# Amplifier_6Channels__2024-06-29.net
KiCad netlist of a schematic drawn in EasyEDA Pro
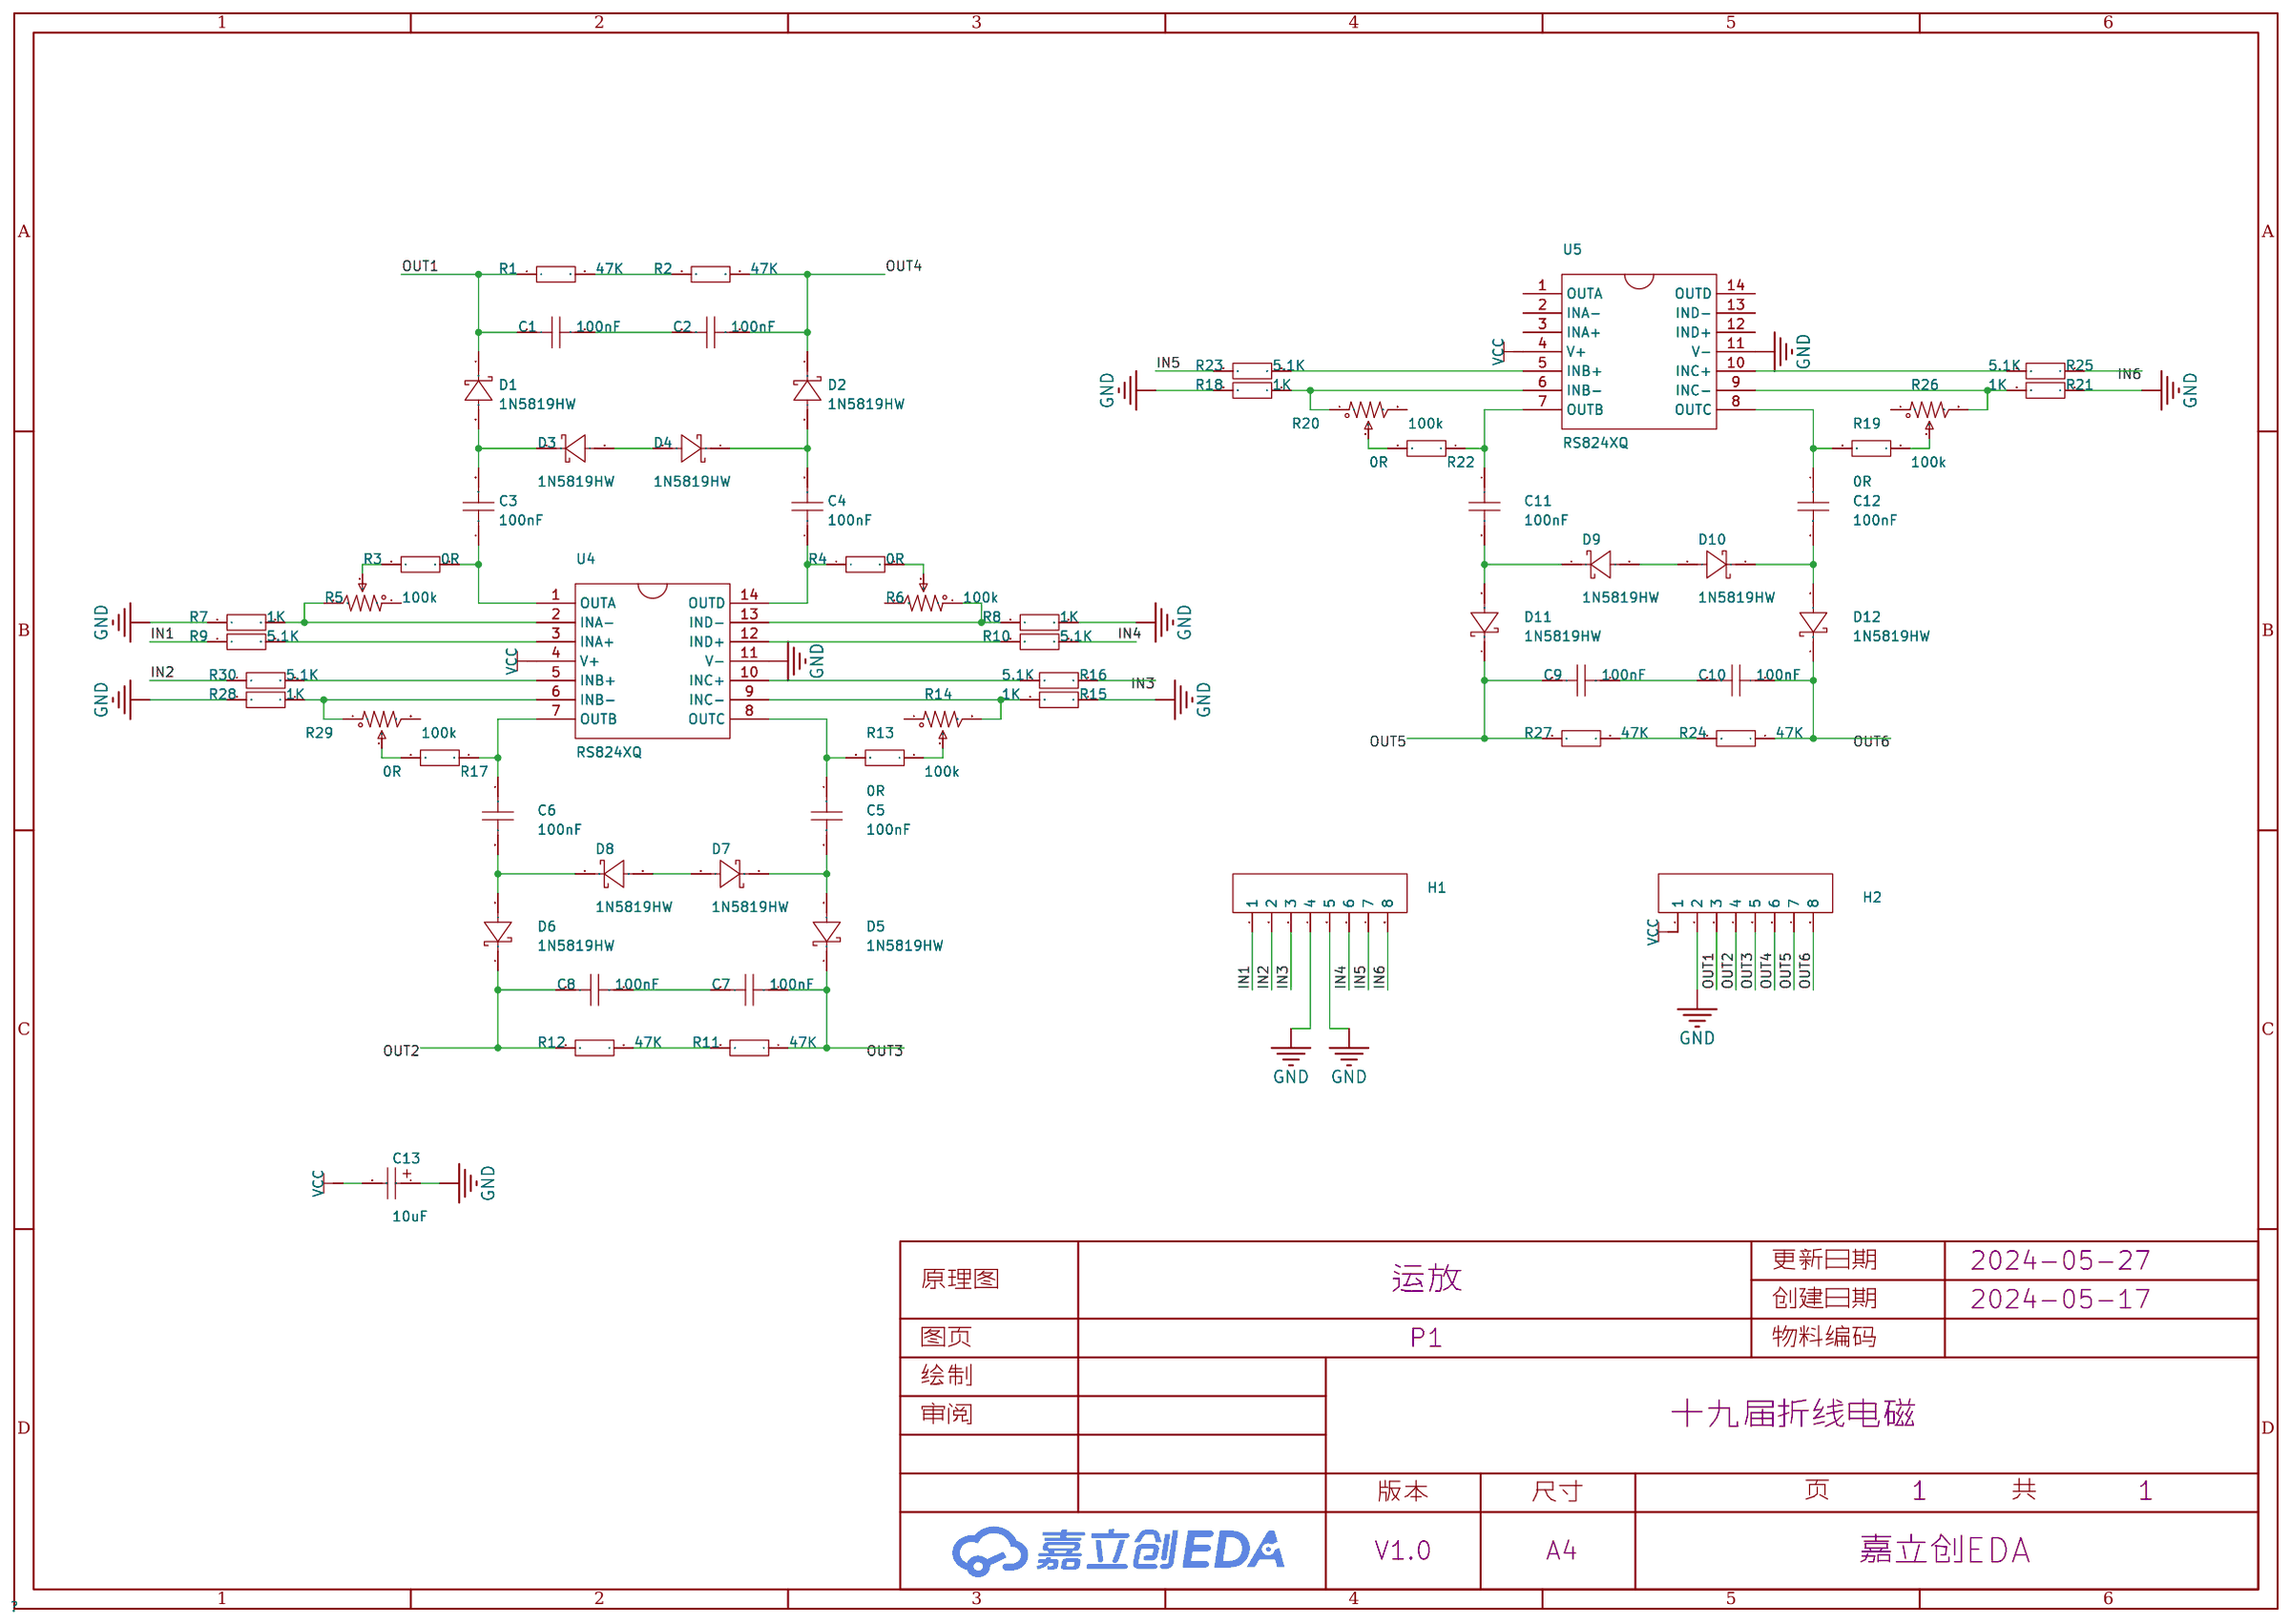
[diagram p0: schematic sheet]

(export (version "E")
  (design (tool "Eeschema 10.0.6"))
  (components
    (comp (ref "C1")
      (value "100nF")
      (footprint "easyedapro:C0603")
      (libsource (lib "easyedapro") (part "CapAcitance"))
    )
    (comp (ref "C2")
      (value "100nF")
      (footprint "easyedapro:C0603")
      (libsource (lib "easyedapro") (part "CapAcitance"))
    )
    (comp (ref "C3")
      (value "100nF")
      (footprint "easyedapro:C0603")
      (libsource (lib "easyedapro") (part "CapAcitance"))
    )
    (comp (ref "C4")
      (value "100nF")
      (footprint "easyedapro:C0603")
      (libsource (lib "easyedapro") (part "CapAcitance"))
    )
    (comp (ref "C5")
      (value "100nF")
      (footprint "easyedapro:C0603")
      (libsource (lib "easyedapro") (part "CapAcitance"))
    )
    (comp (ref "C6")
      (value "100nF")
      (footprint "easyedapro:C0603")
      (libsource (lib "easyedapro") (part "CapAcitance"))
    )
    (comp (ref "C7")
      (value "100nF")
      (footprint "easyedapro:C0603")
      (libsource (lib "easyedapro") (part "CapAcitance"))
    )
    (comp (ref "C8")
      (value "100nF")
      (footprint "easyedapro:C0603")
      (libsource (lib "easyedapro") (part "CapAcitance"))
    )
    (comp (ref "C9")
      (value "100nF")
      (footprint "easyedapro:C0603")
      (libsource (lib "easyedapro") (part "CapAcitance"))
    )
    (comp (ref "C10")
      (value "100nF")
      (footprint "easyedapro:C0603")
      (libsource (lib "easyedapro") (part "CapAcitance"))
    )
    (comp (ref "C11")
      (value "100nF")
      (footprint "easyedapro:C0603")
      (libsource (lib "easyedapro") (part "CapAcitance"))
    )
    (comp (ref "C12")
      (value "100nF")
      (footprint "easyedapro:C0603")
      (libsource (lib "easyedapro") (part "CapAcitance"))
    )
    (comp (ref "C13")
      (value "10uF")
      (footprint "easyedapro:CAP-SMD_L3.2-W1.6-RD-C7171")
      (description "容值:10uF;精度:±10%;额定电压:16V;等效串联电阻:3Ω@100kHz;")
      (fields (field (name "Manufacturer Part") "TAJA106K016RNJ") (field (name "Manufacturer") "Kyocera AVX"))
      (libsource (lib "easyedapro") (part "TAJA106K016RNJ"))
    )
    (comp (ref "D1")
      (value "1N5819HW")
      (footprint "easyedapro:SOD-123_L2.7-W1.6-LS3.7-RD-1")
      (description "二极管配置:-;正向压降(Vf):900mV@3A;直流反向耐压(Vr):40V;平均整流电流(Io):1A;")
      (fields (field (name "Manufacturer") "TECH PUBLIC(台舟)"))
      (libsource (lib "easyedapro") (part "1N5819HW"))
    )
    (comp (ref "D2")
      (value "1N5819HW")
      (footprint "easyedapro:SOD-123_L2.7-W1.6-LS3.7-RD-1")
      (description "二极管配置:-;正向压降(Vf):900mV@3A;直流反向耐压(Vr):40V;平均整流电流(Io):1A;")
      (fields (field (name "Manufacturer") "TECH PUBLIC(台舟)"))
      (libsource (lib "easyedapro") (part "1N5819HW"))
    )
    (comp (ref "D3")
      (value "1N5819HW")
      (footprint "easyedapro:SOD-123_L2.7-W1.6-LS3.7-RD-1")
      (description "二极管配置:-;正向压降(Vf):900mV@3A;直流反向耐压(Vr):40V;平均整流电流(Io):1A;")
      (fields (field (name "Manufacturer") "TECH PUBLIC(台舟)"))
      (libsource (lib "easyedapro") (part "1N5819HW"))
    )
    (comp (ref "D4")
      (value "1N5819HW")
      (footprint "easyedapro:SOD-123_L2.7-W1.6-LS3.7-RD-1")
      (description "二极管配置:-;正向压降(Vf):900mV@3A;直流反向耐压(Vr):40V;平均整流电流(Io):1A;")
      (fields (field (name "Manufacturer") "TECH PUBLIC(台舟)"))
      (libsource (lib "easyedapro") (part "1N5819HW"))
    )
    (comp (ref "D5")
      (value "1N5819HW")
      (footprint "easyedapro:SOD-123_L2.7-W1.6-LS3.7-RD-1")
      (description "二极管配置:-;正向压降(Vf):900mV@3A;直流反向耐压(Vr):40V;平均整流电流(Io):1A;")
      (fields (field (name "Manufacturer") "TECH PUBLIC(台舟)"))
      (libsource (lib "easyedapro") (part "1N5819HW"))
    )
    (comp (ref "D6")
      (value "1N5819HW")
      (footprint "easyedapro:SOD-123_L2.7-W1.6-LS3.7-RD-1")
      (description "二极管配置:-;正向压降(Vf):900mV@3A;直流反向耐压(Vr):40V;平均整流电流(Io):1A;")
      (fields (field (name "Manufacturer") "TECH PUBLIC(台舟)"))
      (libsource (lib "easyedapro") (part "1N5819HW"))
    )
    (comp (ref "D7")
      (value "1N5819HW")
      (footprint "easyedapro:SOD-123_L2.7-W1.6-LS3.7-RD-1")
      (description "二极管配置:-;正向压降(Vf):900mV@3A;直流反向耐压(Vr):40V;平均整流电流(Io):1A;")
      (fields (field (name "Manufacturer") "TECH PUBLIC(台舟)"))
      (libsource (lib "easyedapro") (part "1N5819HW"))
    )
    (comp (ref "D8")
      (value "1N5819HW")
      (footprint "easyedapro:SOD-123_L2.7-W1.6-LS3.7-RD-1")
      (description "二极管配置:-;正向压降(Vf):900mV@3A;直流反向耐压(Vr):40V;平均整流电流(Io):1A;")
      (fields (field (name "Manufacturer") "TECH PUBLIC(台舟)"))
      (libsource (lib "easyedapro") (part "1N5819HW"))
    )
    (comp (ref "D9")
      (value "1N5819HW")
      (footprint "easyedapro:SOD-123_L2.7-W1.6-LS3.7-RD-1")
      (description "二极管配置:-;正向压降(Vf):900mV@3A;直流反向耐压(Vr):40V;平均整流电流(Io):1A;")
      (fields (field (name "Manufacturer") "TECH PUBLIC(台舟)"))
      (libsource (lib "easyedapro") (part "1N5819HW"))
    )
    (comp (ref "D10")
      (value "1N5819HW")
      (footprint "easyedapro:SOD-123_L2.7-W1.6-LS3.7-RD-1")
      (description "二极管配置:-;正向压降(Vf):900mV@3A;直流反向耐压(Vr):40V;平均整流电流(Io):1A;")
      (fields (field (name "Manufacturer") "TECH PUBLIC(台舟)"))
      (libsource (lib "easyedapro") (part "1N5819HW"))
    )
    (comp (ref "D11")
      (value "1N5819HW")
      (footprint "easyedapro:SOD-123_L2.7-W1.6-LS3.7-RD-1")
      (description "二极管配置:-;正向压降(Vf):900mV@3A;直流反向耐压(Vr):40V;平均整流电流(Io):1A;")
      (fields (field (name "Manufacturer") "TECH PUBLIC(台舟)"))
      (libsource (lib "easyedapro") (part "1N5819HW"))
    )
    (comp (ref "D12")
      (value "1N5819HW")
      (footprint "easyedapro:SOD-123_L2.7-W1.6-LS3.7-RD-1")
      (description "二极管配置:-;正向压降(Vf):900mV@3A;直流反向耐压(Vr):40V;平均整流电流(Io):1A;")
      (fields (field (name "Manufacturer") "TECH PUBLIC(台舟)"))
      (libsource (lib "easyedapro") (part "1N5819HW"))
    )
    (comp (ref "H1")
      (value "~")
      (footprint "easyedapro:HDR-TH_8P-P2.54-V-F-1")
      (libsource (lib "easyedapro") (part "Header-Female-2.54_1x8"))
    )
    (comp (ref "H2")
      (value "~")
      (footprint "easyedapro:HDR-TH_8P-P2.54-V-F-1")
      (libsource (lib "easyedapro") (part "Header-Female-2.54_1x8"))
    )
    (comp (ref "R1") (value "47K") (footprint "easyedapro:R0603") (libsource (lib "easyedapro") (part "电阻")))
    (comp (ref "R2") (value "47K") (footprint "easyedapro:R0603") (libsource (lib "easyedapro") (part "电阻")))
    (comp (ref "R3") (value "0R") (footprint "easyedapro:R0603") (libsource (lib "easyedapro") (part "电阻")))
    (comp (ref "R4") (value "0R") (footprint "easyedapro:R0603") (libsource (lib "easyedapro") (part "电阻")))
    (comp (ref "R5")
      (value "100k")
      (footprint "easyedapro:RES-ADJ-TH_3P-L9.5-W4.85-P2.50-BL-BS")
      (description "阻值:50kΩ;精度:±10%;")
      (fields (field (name "Manufacturer Part") "3296W-1-503") (field (name "Manufacturer") "BOCHEN(博晨)"))
      (libsource (lib "easyedapro") (part "可调电阻"))
    )
    (comp (ref "R6")
      (value "100k")
      (footprint "easyedapro:RES-ADJ-TH_3P-L9.5-W4.85-P2.50-BL-BS")
      (description "阻值:50kΩ;精度:±10%;")
      (fields (field (name "Manufacturer Part") "3296W-1-503") (field (name "Manufacturer") "BOCHEN(博晨)"))
      (libsource (lib "easyedapro") (part "可调电阻"))
    )
    (comp (ref "R7") (value "1K") (footprint "easyedapro:R0603") (libsource (lib "easyedapro") (part "电阻")))
    (comp (ref "R8") (value "1K") (footprint "easyedapro:R0603") (libsource (lib "easyedapro") (part "电阻")))
    (comp (ref "R9") (value "5.1K") (footprint "easyedapro:R0603") (libsource (lib "easyedapro") (part "电阻")))
    (comp (ref "R10")
      (value "5.1K")
      (footprint "easyedapro:R0603")
      (libsource (lib "easyedapro") (part "电阻"))
    )
    (comp (ref "R11") (value "47K") (footprint "easyedapro:R0603") (libsource (lib "easyedapro") (part "电阻")))
    (comp (ref "R12") (value "47K") (footprint "easyedapro:R0603") (libsource (lib "easyedapro") (part "电阻")))
    (comp (ref "R13") (value "0R") (footprint "easyedapro:R0603") (libsource (lib "easyedapro") (part "电阻")))
    (comp (ref "R14")
      (value "100k")
      (footprint "easyedapro:RES-ADJ-TH_3P-L9.5-W4.85-P2.50-BL-BS")
      (description "阻值:50kΩ;精度:±10%;")
      (fields (field (name "Manufacturer Part") "3296W-1-503") (field (name "Manufacturer") "BOCHEN(博晨)"))
      (libsource (lib "easyedapro") (part "可调电阻"))
    )
    (comp (ref "R15") (value "1K") (footprint "easyedapro:R0603") (libsource (lib "easyedapro") (part "电阻")))
    (comp (ref "R16")
      (value "5.1K")
      (footprint "easyedapro:R0603")
      (libsource (lib "easyedapro") (part "电阻"))
    )
    (comp (ref "R17") (value "0R") (footprint "easyedapro:R0603") (libsource (lib "easyedapro") (part "电阻")))
    (comp (ref "R18") (value "1K") (footprint "easyedapro:R0603") (libsource (lib "easyedapro") (part "电阻")))
    (comp (ref "R19") (value "0R") (footprint "easyedapro:R0603") (libsource (lib "easyedapro") (part "电阻")))
    (comp (ref "R20")
      (value "100k")
      (footprint "easyedapro:RES-ADJ-TH_3P-L9.5-W4.85-P2.50-BL-BS")
      (description "阻值:50kΩ;精度:±10%;")
      (fields (field (name "Manufacturer Part") "3296W-1-503") (field (name "Manufacturer") "BOCHEN(博晨)"))
      (libsource (lib "easyedapro") (part "可调电阻"))
    )
    (comp (ref "R21") (value "1K") (footprint "easyedapro:R0603") (libsource (lib "easyedapro") (part "电阻")))
    (comp (ref "R22") (value "0R") (footprint "easyedapro:R0603") (libsource (lib "easyedapro") (part "电阻")))
    (comp (ref "R23")
      (value "5.1K")
      (footprint "easyedapro:R0603")
      (libsource (lib "easyedapro") (part "电阻"))
    )
    (comp (ref "R24") (value "47K") (footprint "easyedapro:R0603") (libsource (lib "easyedapro") (part "电阻")))
    (comp (ref "R25")
      (value "5.1K")
      (footprint "easyedapro:R0603")
      (libsource (lib "easyedapro") (part "电阻"))
    )
    (comp (ref "R26")
      (value "100k")
      (footprint "easyedapro:RES-ADJ-TH_3P-L9.5-W4.85-P2.50-BL-BS")
      (description "阻值:50kΩ;精度:±10%;")
      (fields (field (name "Manufacturer Part") "3296W-1-503") (field (name "Manufacturer") "BOCHEN(博晨)"))
      (libsource (lib "easyedapro") (part "可调电阻"))
    )
    (comp (ref "R27") (value "47K") (footprint "easyedapro:R0603") (libsource (lib "easyedapro") (part "电阻")))
    (comp (ref "R28") (value "1K") (footprint "easyedapro:R0603") (libsource (lib "easyedapro") (part "电阻")))
    (comp (ref "R29")
      (value "100k")
      (footprint "easyedapro:RES-ADJ-TH_3P-L9.5-W4.85-P2.50-BL-BS")
      (description "阻值:50kΩ;精度:±10%;")
      (fields (field (name "Manufacturer Part") "3296W-1-503") (field (name "Manufacturer") "BOCHEN(博晨)"))
      (libsource (lib "easyedapro") (part "可调电阻"))
    )
    (comp (ref "R30")
      (value "5.1K")
      (footprint "easyedapro:R0603")
      (libsource (lib "easyedapro") (part "电阻"))
    )
    (comp (ref "U4")
      (value "RS824XQ")
      (footprint "easyedapro:TSSOP-14")
      (libsource (lib "easyedapro") (part "RS824XQ"))
    )
    (comp (ref "U5")
      (value "RS824XQ")
      (footprint "easyedapro:TSSOP-14")
      (libsource (lib "easyedapro") (part "RS824XQ"))
    )
  )
  (nets
    (net (code "1") (name "/IN1") (class "Default")
      (node (ref "H1") (pin "1") (pinfunction "1_1") (pintype "input"))
      (node (ref "R9") (pin "1") (pinfunction "1_1") (pintype "input"))
    )
    (net (code "2") (name "/IN2") (class "Default")
      (node (ref "H1") (pin "2") (pinfunction "2_2") (pintype "input"))
      (node (ref "R30") (pin "1") (pinfunction "1_1") (pintype "input"))
    )
    (net (code "3") (name "/IN3") (class "Default")
      (node (ref "H1") (pin "3") (pinfunction "3_3") (pintype "input"))
      (node (ref "R16") (pin "1") (pinfunction "1_1") (pintype "input"))
    )
    (net (code "4") (name "/IN4") (class "Default")
      (node (ref "H1") (pin "6") (pinfunction "6_6") (pintype "input"))
      (node (ref "R10") (pin "1") (pinfunction "1_1") (pintype "input"))
    )
    (net (code "5") (name "/IN5") (class "Default")
      (node (ref "H1") (pin "7") (pinfunction "7_7") (pintype "input"))
      (node (ref "R23") (pin "1") (pinfunction "1_1") (pintype "input"))
    )
    (net (code "6") (name "/IN6") (class "Default")
      (node (ref "H1") (pin "8") (pinfunction "8_8") (pintype "input"))
      (node (ref "R25") (pin "1") (pinfunction "1_1") (pintype "input"))
    )
    (net (code "7") (name "/OUT1") (class "Default")
      (node (ref "C1") (pin "1") (pinfunction "1_1") (pintype "input"))
      (node (ref "D1") (pin "1") (pinfunction "K_1") (pintype "input"))
      (node (ref "H2") (pin "3") (pinfunction "3_3") (pintype "input"))
      (node (ref "R1") (pin "1") (pinfunction "1_1") (pintype "input"))
    )
    (net (code "8") (name "/OUT2") (class "Default")
      (node (ref "C8") (pin "2") (pinfunction "2_2") (pintype "input"))
      (node (ref "D6") (pin "1") (pinfunction "K_1") (pintype "input"))
      (node (ref "H2") (pin "4") (pinfunction "4_4") (pintype "input"))
      (node (ref "R12") (pin "2") (pinfunction "2_2") (pintype "input"))
    )
    (net (code "9") (name "/OUT3") (class "Default")
      (node (ref "C7") (pin "1") (pinfunction "1_1") (pintype "input"))
      (node (ref "D5") (pin "1") (pinfunction "K_1") (pintype "input"))
      (node (ref "H2") (pin "5") (pinfunction "5_5") (pintype "input"))
      (node (ref "R11") (pin "1") (pinfunction "1_1") (pintype "input"))
    )
    (net (code "10") (name "/OUT4") (class "Default")
      (node (ref "C2") (pin "2") (pinfunction "2_2") (pintype "input"))
      (node (ref "D2") (pin "1") (pinfunction "K_1") (pintype "input"))
      (node (ref "H2") (pin "6") (pinfunction "6_6") (pintype "input"))
      (node (ref "R2") (pin "2") (pinfunction "2_2") (pintype "input"))
    )
    (net (code "11") (name "/OUT5") (class "Default")
      (node (ref "C9") (pin "2") (pinfunction "2_2") (pintype "input"))
      (node (ref "D11") (pin "1") (pinfunction "K_1") (pintype "input"))
      (node (ref "H2") (pin "7") (pinfunction "7_7") (pintype "input"))
      (node (ref "R27") (pin "2") (pinfunction "2_2") (pintype "input"))
    )
    (net (code "12") (name "/OUT6") (class "Default")
      (node (ref "C10") (pin "1") (pinfunction "1_1") (pintype "input"))
      (node (ref "D12") (pin "1") (pinfunction "K_1") (pintype "input"))
      (node (ref "H2") (pin "8") (pinfunction "8_8") (pintype "input"))
      (node (ref "R24") (pin "1") (pinfunction "1_1") (pintype "input"))
    )
    (net (code "13") (name "GND") (class "Default")
      (node (ref "C13") (pin "1") (pinfunction "1_1") (pintype "input"))
      (node (ref "H1") (pin "4") (pinfunction "4_4") (pintype "input"))
      (node (ref "H1") (pin "5") (pinfunction "5_5") (pintype "input"))
      (node (ref "H2") (pin "2") (pinfunction "2_2") (pintype "input"))
      (node (ref "R15") (pin "1") (pinfunction "1_1") (pintype "input"))
      (node (ref "R18") (pin "2") (pinfunction "2_2") (pintype "input"))
      (node (ref "R21") (pin "1") (pinfunction "1_1") (pintype "input"))
      (node (ref "R28") (pin "2") (pinfunction "2_2") (pintype "input"))
      (node (ref "R7") (pin "1") (pinfunction "1_1") (pintype "input"))
      (node (ref "R8") (pin "2") (pinfunction "2_2") (pintype "input"))
      (node (ref "U4") (pin "11") (pinfunction "V-_11") (pintype "input"))
      (node (ref "U5") (pin "11") (pinfunction "V-_11") (pintype "input"))
    )
    (net (code "14") (name "Net-(C1-Pad2)") (class "Default")
      (node (ref "C1") (pin "2") (pinfunction "2_2") (pintype "input"))
      (node (ref "C2") (pin "1") (pinfunction "1_1") (pintype "input"))
    )
    (net (code "15") (name "Net-(C7-Pad2)") (class "Default")
      (node (ref "C7") (pin "2") (pinfunction "2_2") (pintype "input"))
      (node (ref "C8") (pin "1") (pinfunction "1_1") (pintype "input"))
    )
    (net (code "16") (name "Net-(C10-Pad2)") (class "Default")
      (node (ref "C10") (pin "2") (pinfunction "2_2") (pintype "input"))
      (node (ref "C9") (pin "1") (pinfunction "1_1") (pintype "input"))
    )
    (net (code "17") (name "Net-(D1-A)") (class "Default")
      (node (ref "C3") (pin "2") (pinfunction "2_2") (pintype "input"))
      (node (ref "D1") (pin "2") (pinfunction "A_2") (pintype "input"))
      (node (ref "D3") (pin "1") (pinfunction "K_1") (pintype "input"))
    )
    (net (code "18") (name "Net-(D2-A)") (class "Default")
      (node (ref "C4") (pin "2") (pinfunction "2_2") (pintype "input"))
      (node (ref "D2") (pin "2") (pinfunction "A_2") (pintype "input"))
      (node (ref "D4") (pin "1") (pinfunction "K_1") (pintype "input"))
    )
    (net (code "19") (name "Net-(D3-A)") (class "Default")
      (node (ref "D3") (pin "2") (pinfunction "A_2") (pintype "input"))
      (node (ref "D4") (pin "2") (pinfunction "A_2") (pintype "input"))
    )
    (net (code "20") (name "Net-(D5-A)") (class "Default")
      (node (ref "C5") (pin "2") (pinfunction "2_2") (pintype "input"))
      (node (ref "D5") (pin "2") (pinfunction "A_2") (pintype "input"))
      (node (ref "D7") (pin "1") (pinfunction "K_1") (pintype "input"))
    )
    (net (code "21") (name "Net-(D6-A)") (class "Default")
      (node (ref "C6") (pin "2") (pinfunction "2_2") (pintype "input"))
      (node (ref "D6") (pin "2") (pinfunction "A_2") (pintype "input"))
      (node (ref "D8") (pin "1") (pinfunction "K_1") (pintype "input"))
    )
    (net (code "22") (name "Net-(D7-A)") (class "Default")
      (node (ref "D7") (pin "2") (pinfunction "A_2") (pintype "input"))
      (node (ref "D8") (pin "2") (pinfunction "A_2") (pintype "input"))
    )
    (net (code "23") (name "Net-(D10-A)") (class "Default")
      (node (ref "D10") (pin "2") (pinfunction "A_2") (pintype "input"))
      (node (ref "D9") (pin "2") (pinfunction "A_2") (pintype "input"))
    )
    (net (code "24") (name "Net-(D10-K)") (class "Default")
      (node (ref "C12") (pin "2") (pinfunction "2_2") (pintype "input"))
      (node (ref "D10") (pin "1") (pinfunction "K_1") (pintype "input"))
      (node (ref "D12") (pin "2") (pinfunction "A_2") (pintype "input"))
    )
    (net (code "25") (name "Net-(D11-A)") (class "Default")
      (node (ref "C11") (pin "2") (pinfunction "2_2") (pintype "input"))
      (node (ref "D11") (pin "2") (pinfunction "A_2") (pintype "input"))
      (node (ref "D9") (pin "1") (pinfunction "K_1") (pintype "input"))
    )
    (net (code "26") (name "Net-(R1-Pad2)") (class "Default")
      (node (ref "R1") (pin "2") (pinfunction "2_2") (pintype "input"))
      (node (ref "R2") (pin "1") (pinfunction "1_1") (pintype "input"))
    )
    (net (code "27") (name "Net-(R3-Pad1)") (class "Default")
      (node (ref "R3") (pin "1") (pinfunction "1_1") (pintype "input"))
      (node (ref "R5") (pin "2") (pinfunction "2_2") (pintype "input"))
    )
    (net (code "28") (name "Net-(R4-Pad2)") (class "Default")
      (node (ref "R4") (pin "2") (pinfunction "2_2") (pintype "input"))
      (node (ref "R6") (pin "2") (pinfunction "2_2") (pintype "input"))
    )
    (net (code "29") (name "Net-(R11-Pad2)") (class "Default")
      (node (ref "R11") (pin "2") (pinfunction "2_2") (pintype "input"))
      (node (ref "R12") (pin "1") (pinfunction "1_1") (pintype "input"))
    )
    (net (code "30") (name "Net-(R13-Pad1)") (class "Default")
      (node (ref "R13") (pin "1") (pinfunction "1_1") (pintype "input"))
      (node (ref "R14") (pin "2") (pinfunction "2_2") (pintype "input"))
    )
    (net (code "31") (name "Net-(R17-Pad2)") (class "Default")
      (node (ref "R17") (pin "2") (pinfunction "2_2") (pintype "input"))
      (node (ref "R29") (pin "2") (pinfunction "2_2") (pintype "input"))
    )
    (net (code "32") (name "Net-(R19-Pad1)") (class "Default")
      (node (ref "R19") (pin "1") (pinfunction "1_1") (pintype "input"))
      (node (ref "R26") (pin "2") (pinfunction "2_2") (pintype "input"))
    )
    (net (code "33") (name "Net-(R20-Pad2)") (class "Default")
      (node (ref "R20") (pin "2") (pinfunction "2_2") (pintype "input"))
      (node (ref "R22") (pin "2") (pinfunction "2_2") (pintype "input"))
    )
    (net (code "34") (name "Net-(R24-Pad2)") (class "Default")
      (node (ref "R24") (pin "2") (pinfunction "2_2") (pintype "input"))
      (node (ref "R27") (pin "1") (pinfunction "1_1") (pintype "input"))
    )
    (net (code "35") (name "Net-(U4-INA+)") (class "Default")
      (node (ref "R9") (pin "2") (pinfunction "2_2") (pintype "input"))
      (node (ref "U4") (pin "3") (pinfunction "INA+_3") (pintype "input"))
    )
    (net (code "36") (name "Net-(U4-INA-)") (class "Default")
      (node (ref "R5") (pin "3") (pinfunction "3_3") (pintype "input"))
      (node (ref "R7") (pin "2") (pinfunction "2_2") (pintype "input"))
      (node (ref "U4") (pin "2") (pinfunction "INA-_2") (pintype "input"))
    )
    (net (code "37") (name "Net-(U4-INB+)") (class "Default")
      (node (ref "R30") (pin "2") (pinfunction "2_2") (pintype "input"))
      (node (ref "U4") (pin "5") (pinfunction "INB+_5") (pintype "input"))
    )
    (net (code "38") (name "Net-(U4-INB-)") (class "Default")
      (node (ref "R28") (pin "1") (pinfunction "1_1") (pintype "input"))
      (node (ref "R29") (pin "1") (pinfunction "1_1") (pintype "input"))
      (node (ref "U4") (pin "6") (pinfunction "INB-_6") (pintype "input"))
    )
    (net (code "39") (name "Net-(U4-INC+)") (class "Default")
      (node (ref "R16") (pin "2") (pinfunction "2_2") (pintype "input"))
      (node (ref "U4") (pin "10") (pinfunction "INC+_10") (pintype "input"))
    )
    (net (code "40") (name "Net-(U4-INC-)") (class "Default")
      (node (ref "R14") (pin "3") (pinfunction "3_3") (pintype "input"))
      (node (ref "R15") (pin "2") (pinfunction "2_2") (pintype "input"))
      (node (ref "U4") (pin "9") (pinfunction "INC-_9") (pintype "input"))
    )
    (net (code "41") (name "Net-(U4-IND+)") (class "Default")
      (node (ref "R10") (pin "2") (pinfunction "2_2") (pintype "input"))
      (node (ref "U4") (pin "12") (pinfunction "IND+_12") (pintype "input"))
    )
    (net (code "42") (name "Net-(U4-IND-)") (class "Default")
      (node (ref "R6") (pin "1") (pinfunction "1_1") (pintype "input"))
      (node (ref "R8") (pin "1") (pinfunction "1_1") (pintype "input"))
      (node (ref "U4") (pin "13") (pinfunction "IND-_13") (pintype "input"))
    )
    (net (code "43") (name "Net-(U4-OUTA)") (class "Default")
      (node (ref "C3") (pin "1") (pinfunction "1_1") (pintype "input"))
      (node (ref "R3") (pin "2") (pinfunction "2_2") (pintype "input"))
      (node (ref "U4") (pin "1") (pinfunction "OUTA_1") (pintype "input"))
    )
    (net (code "44") (name "Net-(U4-OUTB)") (class "Default")
      (node (ref "C6") (pin "1") (pinfunction "1_1") (pintype "input"))
      (node (ref "R17") (pin "1") (pinfunction "1_1") (pintype "input"))
      (node (ref "U4") (pin "7") (pinfunction "OUTB_7") (pintype "input"))
    )
    (net (code "45") (name "Net-(U4-OUTC)") (class "Default")
      (node (ref "C5") (pin "1") (pinfunction "1_1") (pintype "input"))
      (node (ref "R13") (pin "2") (pinfunction "2_2") (pintype "input"))
      (node (ref "U4") (pin "8") (pinfunction "OUTC_8") (pintype "input"))
    )
    (net (code "46") (name "Net-(U4-OUTD)") (class "Default")
      (node (ref "C4") (pin "1") (pinfunction "1_1") (pintype "input"))
      (node (ref "R4") (pin "1") (pinfunction "1_1") (pintype "input"))
      (node (ref "U4") (pin "14") (pinfunction "OUTD_14") (pintype "input"))
    )
    (net (code "47") (name "Net-(U5-INB+)") (class "Default")
      (node (ref "R23") (pin "2") (pinfunction "2_2") (pintype "input"))
      (node (ref "U5") (pin "5") (pinfunction "INB+_5") (pintype "input"))
    )
    (net (code "48") (name "Net-(U5-INB-)") (class "Default")
      (node (ref "R18") (pin "1") (pinfunction "1_1") (pintype "input"))
      (node (ref "R20") (pin "1") (pinfunction "1_1") (pintype "input"))
      (node (ref "U5") (pin "6") (pinfunction "INB-_6") (pintype "input"))
    )
    (net (code "49") (name "Net-(U5-INC+)") (class "Default")
      (node (ref "R25") (pin "2") (pinfunction "2_2") (pintype "input"))
      (node (ref "U5") (pin "10") (pinfunction "INC+_10") (pintype "input"))
    )
    (net (code "50") (name "Net-(U5-INC-)") (class "Default")
      (node (ref "R21") (pin "2") (pinfunction "2_2") (pintype "input"))
      (node (ref "R26") (pin "3") (pinfunction "3_3") (pintype "input"))
      (node (ref "U5") (pin "9") (pinfunction "INC-_9") (pintype "input"))
    )
    (net (code "51") (name "Net-(U5-OUTB)") (class "Default")
      (node (ref "C11") (pin "1") (pinfunction "1_1") (pintype "input"))
      (node (ref "R22") (pin "1") (pinfunction "1_1") (pintype "input"))
      (node (ref "U5") (pin "7") (pinfunction "OUTB_7") (pintype "input"))
    )
    (net (code "52") (name "Net-(U5-OUTC)") (class "Default")
      (node (ref "C12") (pin "1") (pinfunction "1_1") (pintype "input"))
      (node (ref "R19") (pin "2") (pinfunction "2_2") (pintype "input"))
      (node (ref "U5") (pin "8") (pinfunction "OUTC_8") (pintype "input"))
    )
    (net (code "53") (name "VCC") (class "Default")
      (node (ref "C13") (pin "2") (pinfunction "2_2") (pintype "input"))
      (node (ref "H2") (pin "1") (pinfunction "1_1") (pintype "input"))
      (node (ref "U4") (pin "4") (pinfunction "V+_4") (pintype "input"))
      (node (ref "U5") (pin "4") (pinfunction "V+_4") (pintype "input"))
    )
    (net (code "54") (name "unconnected-(R5-Pad1)") (class "Default")
      (node (ref "R5") (pin "1") (pinfunction "1_1") (pintype "input"))
    )
    (net (code "55") (name "unconnected-(R6-Pad3)") (class "Default")
      (node (ref "R6") (pin "3") (pinfunction "3_3") (pintype "input"))
    )
    (net (code "56") (name "unconnected-(R14-Pad1)") (class "Default")
      (node (ref "R14") (pin "1") (pinfunction "1_1") (pintype "input"))
    )
    (net (code "57") (name "unconnected-(R20-Pad3)") (class "Default")
      (node (ref "R20") (pin "3") (pinfunction "3_3") (pintype "input"))
    )
    (net (code "58") (name "unconnected-(R26-Pad1)") (class "Default")
      (node (ref "R26") (pin "1") (pinfunction "1_1") (pintype "input"))
    )
    (net (code "59") (name "unconnected-(R29-Pad3)") (class "Default")
      (node (ref "R29") (pin "3") (pinfunction "3_3") (pintype "input"))
    )
    (net (code "60") (name "unconnected-(U5-INA+-Pad3)") (class "Default")
      (node (ref "U5") (pin "3") (pinfunction "INA+_3") (pintype "input"))
    )
    (net (code "61") (name "unconnected-(U5-INA--Pad2)") (class "Default")
      (node (ref "U5") (pin "2") (pinfunction "INA-_2") (pintype "input"))
    )
    (net (code "62") (name "unconnected-(U5-IND+-Pad12)") (class "Default")
      (node (ref "U5") (pin "12") (pinfunction "IND+_12") (pintype "input"))
    )
    (net (code "63") (name "unconnected-(U5-IND--Pad13)") (class "Default")
      (node (ref "U5") (pin "13") (pinfunction "IND-_13") (pintype "input"))
    )
    (net (code "64") (name "unconnected-(U5-OUTA-Pad1)") (class "Default")
      (node (ref "U5") (pin "1") (pinfunction "OUTA_1") (pintype "input"))
    )
    (net (code "65") (name "unconnected-(U5-OUTD-Pad14)") (class "Default")
      (node (ref "U5") (pin "14") (pinfunction "OUTD_14") (pintype "input"))
    )
  )
)
